# UniSeb8266.net
KiCad netlist of a schematic drawn in EAGLE
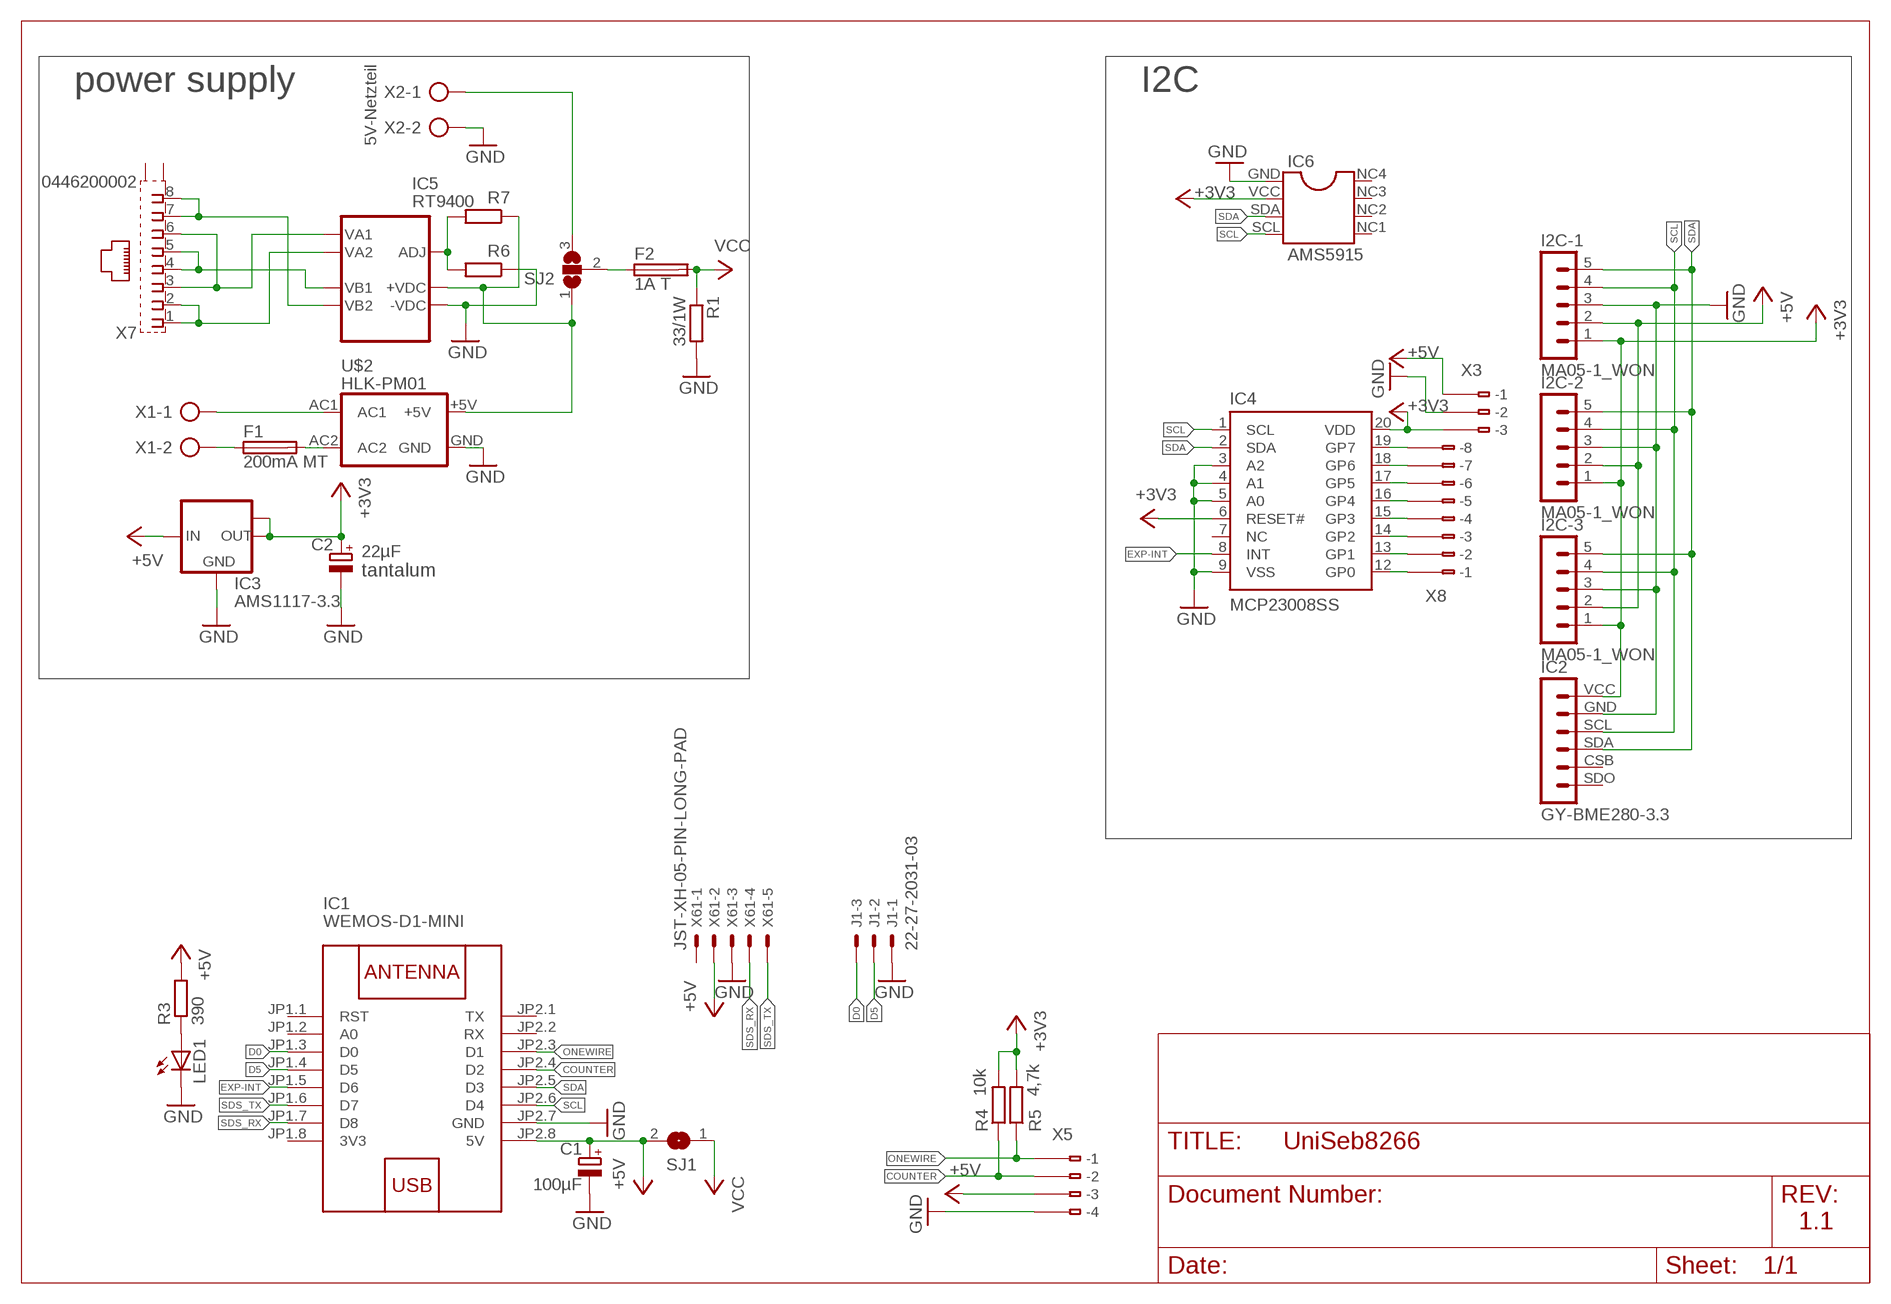
[diagram p0: schematic, sheet 1]

(export (version "E")
  (design (tool "Eeschema 10.0.6"))
  (components
    (comp (ref "C1")
      (value "100µF")
      (footprint "eagle-import:E2,5-6")
      (libsource (lib "eagle-import") (part "CPOL-EUE2.5-6"))
    )
    (comp (ref "C2")
      (value "22µF")
      (footprint "eagle-import:E2,5-6")
      (libsource (lib "eagle-import") (part "CPOL-EUE2.5-6"))
    )
    (comp (ref "F1")
      (value "200mA MT")
      (footprint "eagle-import:TR5")
      (libsource (lib "eagle-import") (part "TR5"))
    )
    (comp (ref "F2")
      (value "1A T")
      (footprint "eagle-import:TR5")
      (libsource (lib "eagle-import") (part "TR5"))
    )
    (comp (ref "I2C-1")
      (value "MA05-1_WON")
      (footprint "eagle-import:MA05-1_WON")
      (libsource (lib "eagle-import") (part "MA05-1_WON"))
    )
    (comp (ref "I2C-2")
      (value "MA05-1_WON")
      (footprint "eagle-import:MA05-1_WON")
      (libsource (lib "eagle-import") (part "MA05-1_WON"))
    )
    (comp (ref "I2C-3")
      (value "MA05-1_WON")
      (footprint "eagle-import:MA05-1_WON")
      (libsource (lib "eagle-import") (part "MA05-1_WON"))
    )
    (comp (ref "IC1")
      (value "WEMOS-D1-MINI")
      (footprint "eagle-import:WEMOS-D1-MINI")
      (libsource (lib "eagle-import") (part "WEMOS-D1-MINI"))
    )
    (comp (ref "IC2")
      (value "GY-BME280-3.3")
      (footprint "eagle-import:GY-BME280-3.3")
      (libsource (lib "eagle-import") (part "GY-BME280-3.3"))
    )
    (comp (ref "IC3")
      (value "AMS1117-3.3")
      (footprint "eagle-import:SOT223")
      (libsource (lib "eagle-import") (part "LM1117IMPX-3.3"))
    )
    (comp (ref "IC4")
      (value "MCP23008SS")
      (footprint "eagle-import:SSOP20")
      (libsource (lib "eagle-import") (part "MCP23008SS"))
    )
    (comp (ref "IC5")
      (value "RT9400")
      (footprint "eagle-import:RT9400")
      (libsource (lib "eagle-import") (part "RT9400"))
    )
    (comp (ref "IC6")
      (value "AMS5915")
      (footprint "eagle-import:AMS5915")
      (libsource (lib "eagle-import") (part "AMS5915"))
    )
    (comp (ref "J1")
      (value "22-27-2031-03")
      (footprint "eagle-import:6410-03")
      (libsource (lib "eagle-import") (part "22-?-0327-2031"))
    )
    (comp (ref "LED1")
      (value "LED3MM")
      (footprint "eagle-import:LED3MM")
      (libsource (lib "eagle-import") (part "LED3MM"))
    )
    (comp (ref "R1")
      (value "33/1W")
      (footprint "eagle-import:P0613V")
      (libsource (lib "eagle-import") (part "resistor_R-EU_0613/5V"))
    )
    (comp (ref "R3")
      (value "390")
      (footprint "eagle-import:R1206")
      (libsource (lib "eagle-import") (part "R-EU_R1206"))
    )
    (comp (ref "R4")
      (value "10k")
      (footprint "eagle-import:R1206")
      (libsource (lib "eagle-import") (part "R-EU_R1206"))
    )
    (comp (ref "R5")
      (value "4,7k")
      (footprint "eagle-import:R1206")
      (libsource (lib "eagle-import") (part "R-EU_R1206"))
    )
    (comp (ref "R6")
      (value "R-EU_R1206")
      (footprint "eagle-import:R1206")
      (libsource (lib "eagle-import") (part "R-EU_R1206"))
    )
    (comp (ref "R7")
      (value "R-EU_R1206")
      (footprint "eagle-import:R1206")
      (libsource (lib "eagle-import") (part "R-EU_R1206"))
    )
    (comp (ref "SJ1") (value "SJ") (footprint "eagle-import:SJ") (libsource (lib "eagle-import") (part "SJ")))
    (comp (ref "SJ2")
      (value "SJ2W")
      (footprint "eagle-import:SJ_2")
      (libsource (lib "eagle-import") (part "SJ2W"))
    )
    (comp (ref "U$2")
      (value "HLK-PM01")
      (footprint "eagle-import:HLK-PM01")
      (libsource (lib "eagle-import") (part "HLK-PM01"))
    )
    (comp (ref "X1")
      (value "AK500/2")
      (footprint "eagle-import:AK500_2")
      (libsource (lib "eagle-import") (part "AK500/2"))
    )
    (comp (ref "X2")
      (value "AK500/2")
      (footprint "eagle-import:AK500_2")
      (libsource (lib "eagle-import") (part "AK500/2"))
    )
    (comp (ref "X3")
      (value "233-503")
      (footprint "eagle-import:233-503")
      (fields (field (name "MF") "Wago Corporation") (field (name "MPN") "0233-0503"))
      (libsource (lib "eagle-import") (part "233-503"))
    )
    (comp (ref "X5")
      (value "233-504")
      (footprint "eagle-import:233-504")
      (fields (field (name "MF") "Wago Corporation") (field (name "MPN") "0233-0504"))
      (libsource (lib "eagle-import") (part "233-504"))
    )
    (comp (ref "X7")
      (value "0446200002")
      (footprint "eagle-import:0446200002")
      (fields (field (name "MF") "MOLEX"))
      (libsource (lib "eagle-import") (part "0446200002"))
    )
    (comp (ref "X8")
      (value "233-508")
      (footprint "eagle-import:233-508")
      (fields (field (name "MF") "Wago Corporation") (field (name "MPN") "0233-0508"))
      (libsource (lib "eagle-import") (part "233-508"))
    )
    (comp (ref "X61")
      (value "JST-XH-05-PIN-LONG-PAD")
      (footprint "eagle-import:JST-XH-05-PACKAGE-LONG-PAD")
      (libsource (lib "eagle-import") (part "JST-XH-05-PIN-LONG-PAD"))
    )
  )
  (nets
    (net (code "1") (name "+3V3") (class "Default")
      (node (ref "C2") (pin "+") (pinfunction "+_+") (pintype "passive"))
      (node (ref "I2C-1") (pin "1") (pinfunction "1_1") (pintype "passive"))
      (node (ref "I2C-2") (pin "1") (pinfunction "1_1") (pintype "passive"))
      (node (ref "I2C-3") (pin "1") (pinfunction "1_1") (pintype "passive"))
      (node (ref "IC2") (pin "VCC") (pinfunction "VCC_VCC") (pintype "passive"))
      (node (ref "IC3") (pin "2") (pinfunction "OUT_2") (pintype "passive"))
      (node (ref "IC3") (pin "TAB") (pinfunction "OUT1_TAB") (pintype "passive"))
      (node (ref "IC4") (pin "20") (pinfunction "VDD_20") (pintype "power_in"))
      (node (ref "IC4") (pin "6") (pinfunction "RESET#_6") (pintype "input"))
      (node (ref "IC6") (pin "VCC") (pinfunction "2_VCC") (pintype "passive"))
      (node (ref "R4") (pin "2") (pinfunction "2_2") (pintype "passive"))
      (node (ref "R5") (pin "2") (pinfunction "2_2") (pintype "passive"))
      (node (ref "X3") (pin "B3") (pinfunction "B-3_B3") (pintype "passive"))
    )
    (net (code "2") (name "+5V") (class "Default")
      (node (ref "C1") (pin "+") (pinfunction "+_+") (pintype "passive"))
      (node (ref "I2C-1") (pin "2") (pinfunction "2_2") (pintype "passive"))
      (node (ref "I2C-2") (pin "2") (pinfunction "2_2") (pintype "passive"))
      (node (ref "I2C-3") (pin "2") (pinfunction "2_2") (pintype "passive"))
      (node (ref "IC1") (pin "JP2.8") (pinfunction "5V_JP2.8") (pintype "power_in"))
      (node (ref "IC3") (pin "3") (pinfunction "IN_3") (pintype "input"))
      (node (ref "R3") (pin "2") (pinfunction "2_2") (pintype "passive"))
      (node (ref "SJ1") (pin "2") (pinfunction "2_2") (pintype "passive"))
      (node (ref "X3") (pin "B1") (pinfunction "B-1_B1") (pintype "passive"))
      (node (ref "X5") (pin "B3") (pinfunction "B-3_B3") (pintype "passive"))
      (node (ref "X61") (pin "2") (pinfunction "S_2") (pintype "passive"))
    )
    (net (code "3") (name "/3V3") (class "Default")
      (node (ref "IC1") (pin "JP1.8") (pinfunction "3V3_JP1.8") (pintype "power_in"))
    )
    (net (code "4") (name "COUNTER") (class "Default")
      (node (ref "IC1") (pin "JP2.4") (pinfunction "D2_JP2.4") (pintype "bidirectional"))
      (node (ref "R4") (pin "1") (pinfunction "1_1") (pintype "passive"))
      (node (ref "X5") (pin "B2") (pinfunction "B-2_B2") (pintype "passive"))
    )
    (net (code "5") (name "D0") (class "Default")
      (node (ref "IC1") (pin "JP1.3") (pinfunction "D0_JP1.3") (pintype "bidirectional"))
      (node (ref "J1") (pin "3") (pinfunction "S_3") (pintype "passive"))
    )
    (net (code "6") (name "D5") (class "Default")
      (node (ref "IC1") (pin "JP1.4") (pinfunction "D5_JP1.4") (pintype "bidirectional"))
      (node (ref "J1") (pin "2") (pinfunction "S_2") (pintype "passive"))
    )
    (net (code "7") (name "EXP-INT") (class "Default")
      (node (ref "IC1") (pin "JP1.5") (pinfunction "D6_JP1.5") (pintype "bidirectional"))
      (node (ref "IC4") (pin "8") (pinfunction "INT_8") (pintype "output"))
    )
    (net (code "8") (name "GND") (class "Default")
      (node (ref "C1") (pin "-") (pinfunction "-_-") (pintype "passive"))
      (node (ref "C2") (pin "-") (pinfunction "-_-") (pintype "passive"))
      (node (ref "I2C-1") (pin "3") (pinfunction "3_3") (pintype "passive"))
      (node (ref "I2C-2") (pin "3") (pinfunction "3_3") (pintype "passive"))
      (node (ref "I2C-3") (pin "3") (pinfunction "3_3") (pintype "passive"))
      (node (ref "IC1") (pin "JP2.7") (pinfunction "GND_JP2.7") (pintype "power_in"))
      (node (ref "IC2") (pin "GND") (pinfunction "GND_GND") (pintype "passive"))
      (node (ref "IC3") (pin "1") (pinfunction "GND_1") (pintype "input"))
      (node (ref "IC4") (pin "3") (pinfunction "A2_3") (pintype "input"))
      (node (ref "IC4") (pin "4") (pinfunction "A1_4") (pintype "input"))
      (node (ref "IC4") (pin "5") (pinfunction "A0_5") (pintype "input"))
      (node (ref "IC4") (pin "9") (pinfunction "VSS_9") (pintype "power_in"))
      (node (ref "IC5") (pin "P$5") (pinfunction "-VDC_P$5") (pintype "output"))
      (node (ref "IC6") (pin "GND") (pinfunction "1_GND") (pintype "passive"))
      (node (ref "J1") (pin "1") (pinfunction "S_1") (pintype "passive"))
      (node (ref "LED1") (pin "K") (pinfunction "C_K") (pintype "passive"))
      (node (ref "R1") (pin "2") (pinfunction "2_2") (pintype "passive"))
      (node (ref "R6") (pin "1") (pinfunction "1_1") (pintype "passive"))
      (node (ref "U$2") (pin "GND") (pinfunction "GND_GND") (pintype "passive"))
      (node (ref "X2") (pin "2") (pinfunction "KL_2") (pintype "passive"))
      (node (ref "X3") (pin "B2") (pinfunction "B-2_B2") (pintype "passive"))
      (node (ref "X5") (pin "B4") (pinfunction "B-4_B4") (pintype "passive"))
      (node (ref "X61") (pin "3") (pinfunction "S_3") (pintype "passive"))
    )
    (net (code "9") (name "Net-(F1-Pad2)") (class "Default")
      (node (ref "F1") (pin "2") (pinfunction "2_2") (pintype "passive"))
      (node (ref "U$2") (pin "AC2") (pinfunction "AC2_AC2") (pintype "input"))
    )
    (net (code "10") (name "Net-(F2-Pad1)") (class "Default")
      (node (ref "F2") (pin "1") (pinfunction "1_1") (pintype "passive"))
      (node (ref "SJ2") (pin "2") (pinfunction "2_2") (pintype "passive"))
    )
    (net (code "11") (name "Net-(IC4-GP0)") (class "Default")
      (node (ref "IC4") (pin "12") (pinfunction "GP0_12") (pintype "bidirectional"))
      (node (ref "X8") (pin "B1") (pinfunction "B-1_B1") (pintype "passive"))
    )
    (net (code "12") (name "Net-(IC4-GP1)") (class "Default")
      (node (ref "IC4") (pin "13") (pinfunction "GP1_13") (pintype "bidirectional"))
      (node (ref "X8") (pin "B2") (pinfunction "B-2_B2") (pintype "passive"))
    )
    (net (code "13") (name "Net-(IC4-GP2)") (class "Default")
      (node (ref "IC4") (pin "14") (pinfunction "GP2_14") (pintype "bidirectional"))
      (node (ref "X8") (pin "B3") (pinfunction "B-3_B3") (pintype "passive"))
    )
    (net (code "14") (name "Net-(IC4-GP3)") (class "Default")
      (node (ref "IC4") (pin "15") (pinfunction "GP3_15") (pintype "bidirectional"))
      (node (ref "X8") (pin "B4") (pinfunction "B-4_B4") (pintype "passive"))
    )
    (net (code "15") (name "Net-(IC4-GP4)") (class "Default")
      (node (ref "IC4") (pin "16") (pinfunction "GP4_16") (pintype "bidirectional"))
      (node (ref "X8") (pin "B5") (pinfunction "B-5_B5") (pintype "passive"))
    )
    (net (code "16") (name "Net-(IC4-GP5)") (class "Default")
      (node (ref "IC4") (pin "17") (pinfunction "GP5_17") (pintype "bidirectional"))
      (node (ref "X8") (pin "B6") (pinfunction "B-6_B6") (pintype "passive"))
    )
    (net (code "17") (name "Net-(IC4-GP6)") (class "Default")
      (node (ref "IC4") (pin "18") (pinfunction "GP6_18") (pintype "bidirectional"))
      (node (ref "X8") (pin "B7") (pinfunction "B-7_B7") (pintype "passive"))
    )
    (net (code "18") (name "Net-(IC4-GP7)") (class "Default")
      (node (ref "IC4") (pin "19") (pinfunction "GP7_19") (pintype "bidirectional"))
      (node (ref "X8") (pin "B8") (pinfunction "B-8_B8") (pintype "passive"))
    )
    (net (code "19") (name "Net-(IC5-+VDC)") (class "Default")
      (node (ref "IC5") (pin "P$6") (pinfunction "+VDC_P$6") (pintype "output"))
      (node (ref "R7") (pin "1") (pinfunction "1_1") (pintype "passive"))
      (node (ref "SJ2") (pin "1") (pinfunction "1_1") (pintype "passive"))
      (node (ref "U$2") (pin "+5V") (pinfunction "+5V_+5V") (pintype "passive"))
    )
    (net (code "20") (name "Net-(IC5-ADJ)") (class "Default")
      (node (ref "IC5") (pin "P$7") (pinfunction "ADJ_P$7") (pintype "output"))
      (node (ref "R6") (pin "2") (pinfunction "2_2") (pintype "passive"))
      (node (ref "R7") (pin "2") (pinfunction "2_2") (pintype "passive"))
    )
    (net (code "21") (name "Net-(IC5-VA1)") (class "Default")
      (node (ref "IC5") (pin "P$1") (pinfunction "VA1_P$1") (pintype "input"))
      (node (ref "X7") (pin "3") (pinfunction "3_3") (pintype "passive"))
      (node (ref "X7") (pin "6") (pinfunction "6_6") (pintype "passive"))
    )
    (net (code "22") (name "Net-(IC5-VA2)") (class "Default")
      (node (ref "IC5") (pin "P$2") (pinfunction "VA2_P$2") (pintype "input"))
      (node (ref "X7") (pin "1") (pinfunction "1_1") (pintype "passive"))
      (node (ref "X7") (pin "2") (pinfunction "2_2") (pintype "passive"))
    )
    (net (code "23") (name "Net-(IC5-VB1)") (class "Default")
      (node (ref "IC5") (pin "P$3") (pinfunction "VB1_P$3") (pintype "input"))
      (node (ref "X7") (pin "4") (pinfunction "4_4") (pintype "passive"))
      (node (ref "X7") (pin "5") (pinfunction "5_5") (pintype "passive"))
    )
    (net (code "24") (name "Net-(IC5-VB2)") (class "Default")
      (node (ref "IC5") (pin "P$4") (pinfunction "VB2_P$4") (pintype "input"))
      (node (ref "X7") (pin "7") (pinfunction "7_7") (pintype "passive"))
      (node (ref "X7") (pin "8") (pinfunction "8_8") (pintype "passive"))
    )
    (net (code "25") (name "Net-(LED1-PadA)") (class "Default")
      (node (ref "LED1") (pin "A") (pinfunction "A_A") (pintype "passive"))
      (node (ref "R3") (pin "1") (pinfunction "1_1") (pintype "passive"))
    )
    (net (code "26") (name "Net-(X1A-KL)") (class "Default")
      (node (ref "U$2") (pin "AC1") (pinfunction "AC1_AC1") (pintype "input"))
      (node (ref "X1") (pin "1") (pinfunction "KL_1") (pintype "passive"))
    )
    (net (code "27") (name "Net-(X1B-KL)") (class "Default")
      (node (ref "F1") (pin "1") (pinfunction "1_1") (pintype "passive"))
      (node (ref "X1") (pin "2") (pinfunction "KL_2") (pintype "passive"))
    )
    (net (code "28") (name "Net-(X2A-KL)") (class "Default")
      (node (ref "SJ2") (pin "3") (pinfunction "3_3") (pintype "passive"))
      (node (ref "X2") (pin "1") (pinfunction "KL_1") (pintype "passive"))
    )
    (net (code "29") (name "ONEWIRE") (class "Default")
      (node (ref "IC1") (pin "JP2.3") (pinfunction "D1_JP2.3") (pintype "bidirectional"))
      (node (ref "R5") (pin "1") (pinfunction "1_1") (pintype "passive"))
      (node (ref "X5") (pin "B1") (pinfunction "B-1_B1") (pintype "passive"))
    )
    (net (code "30") (name "SCL") (class "Default")
      (node (ref "I2C-1") (pin "4") (pinfunction "4_4") (pintype "passive"))
      (node (ref "I2C-2") (pin "4") (pinfunction "4_4") (pintype "passive"))
      (node (ref "I2C-3") (pin "4") (pinfunction "4_4") (pintype "passive"))
      (node (ref "IC1") (pin "JP2.6") (pinfunction "D4_JP2.6") (pintype "bidirectional"))
      (node (ref "IC2") (pin "SCL") (pinfunction "SCL_SCL") (pintype "passive"))
      (node (ref "IC4") (pin "1") (pinfunction "SCL_1") (pintype "input"))
      (node (ref "IC6") (pin "SCL") (pinfunction "4_SCL") (pintype "passive"))
    )
    (net (code "31") (name "SDA") (class "Default")
      (node (ref "I2C-1") (pin "5") (pinfunction "5_5") (pintype "passive"))
      (node (ref "I2C-2") (pin "5") (pinfunction "5_5") (pintype "passive"))
      (node (ref "I2C-3") (pin "5") (pinfunction "5_5") (pintype "passive"))
      (node (ref "IC1") (pin "JP2.5") (pinfunction "D3_JP2.5") (pintype "bidirectional"))
      (node (ref "IC2") (pin "SDA") (pinfunction "SDA_SDA") (pintype "passive"))
      (node (ref "IC4") (pin "2") (pinfunction "SDA_2") (pintype "bidirectional"))
      (node (ref "IC6") (pin "SDA") (pinfunction "3_SDA") (pintype "passive"))
    )
    (net (code "32") (name "SDS_RX") (class "Default")
      (node (ref "IC1") (pin "JP1.7") (pinfunction "D8_JP1.7") (pintype "bidirectional"))
      (node (ref "X61") (pin "4") (pinfunction "S_4") (pintype "passive"))
    )
    (net (code "33") (name "SDS_TX") (class "Default")
      (node (ref "IC1") (pin "JP1.6") (pinfunction "D7_JP1.6") (pintype "bidirectional"))
      (node (ref "X61") (pin "5") (pinfunction "S_5") (pintype "passive"))
    )
    (net (code "34") (name "VCC") (class "Default")
      (node (ref "F2") (pin "2") (pinfunction "2_2") (pintype "passive"))
      (node (ref "R1") (pin "1") (pinfunction "1_1") (pintype "passive"))
      (node (ref "SJ1") (pin "1") (pinfunction "1_1") (pintype "passive"))
    )
    (net (code "35") (name "unconnected-(IC1-A0-PadJP1.2)") (class "Default")
      (node (ref "IC1") (pin "JP1.2") (pinfunction "A0_JP1.2") (pintype "bidirectional"))
    )
    (net (code "36") (name "unconnected-(IC1-RST-PadJP1.1)") (class "Default")
      (node (ref "IC1") (pin "JP1.1") (pinfunction "RST_JP1.1") (pintype "bidirectional"))
    )
    (net (code "37") (name "unconnected-(IC1-RX-PadJP2.2)") (class "Default")
      (node (ref "IC1") (pin "JP2.2") (pinfunction "RX_JP2.2") (pintype "bidirectional"))
    )
    (net (code "38") (name "unconnected-(IC1-TX-PadJP2.1)") (class "Default")
      (node (ref "IC1") (pin "JP2.1") (pinfunction "TX_JP2.1") (pintype "bidirectional"))
    )
    (net (code "39") (name "unconnected-(IC2-PadCSB)") (class "Default")
      (node (ref "IC2") (pin "CSB") (pinfunction "CSB_CSB") (pintype "passive"))
    )
    (net (code "40") (name "unconnected-(IC2-PadSDO)") (class "Default")
      (node (ref "IC2") (pin "SDO") (pinfunction "SDO_SDO") (pintype "passive"))
    )
    (net (code "41") (name "unconnected-(IC4-NC-Pad7)") (class "Default")
      (node (ref "IC4") (pin "7") (pinfunction "NC_7") (pintype "no_connect"))
    )
    (net (code "42") (name "unconnected-(IC6-5-PadNC1)") (class "Default")
      (node (ref "IC6") (pin "NC1") (pinfunction "5_NC1") (pintype "passive"))
    )
    (net (code "43") (name "unconnected-(IC6-6-PadNC2)") (class "Default")
      (node (ref "IC6") (pin "NC2") (pinfunction "6_NC2") (pintype "passive"))
    )
    (net (code "44") (name "unconnected-(IC6-7-PadNC3)") (class "Default")
      (node (ref "IC6") (pin "NC3") (pinfunction "7_NC3") (pintype "passive"))
    )
    (net (code "45") (name "unconnected-(IC6-8-PadNC4)") (class "Default")
      (node (ref "IC6") (pin "NC4") (pinfunction "8_NC4") (pintype "passive"))
    )
    (net (code "46") (name "unconnected-(X3--1-PadA1)") (class "Default")
      (node (ref "X3") (pin "A1") (pinfunction "-1_A1") (pintype "passive"))
    )
    (net (code "47") (name "unconnected-(X3--2-PadA2)") (class "Default")
      (node (ref "X3") (pin "A2") (pinfunction "-2_A2") (pintype "passive"))
    )
    (net (code "48") (name "unconnected-(X3--3-PadA3)") (class "Default")
      (node (ref "X3") (pin "A3") (pinfunction "-3_A3") (pintype "passive"))
    )
    (net (code "49") (name "unconnected-(X5--1-PadA1)") (class "Default")
      (node (ref "X5") (pin "A1") (pinfunction "-1_A1") (pintype "passive"))
    )
    (net (code "50") (name "unconnected-(X5--2-PadA2)") (class "Default")
      (node (ref "X5") (pin "A2") (pinfunction "-2_A2") (pintype "passive"))
    )
    (net (code "51") (name "unconnected-(X5--3-PadA3)") (class "Default")
      (node (ref "X5") (pin "A3") (pinfunction "-3_A3") (pintype "passive"))
    )
    (net (code "52") (name "unconnected-(X5--4-PadA4)") (class "Default")
      (node (ref "X5") (pin "A4") (pinfunction "-4_A4") (pintype "passive"))
    )
    (net (code "53") (name "unconnected-(X7-S1-PadS@1)") (class "Default")
      (node (ref "X7") (pin "S@1") (pinfunction "S1_S@1") (pintype "passive"))
    )
    (net (code "54") (name "unconnected-(X7-S2-PadS@2)") (class "Default")
      (node (ref "X7") (pin "S@2") (pinfunction "S2_S@2") (pintype "passive"))
    )
    (net (code "55") (name "unconnected-(X8--1-PadA1)") (class "Default")
      (node (ref "X8") (pin "A1") (pinfunction "-1_A1") (pintype "passive"))
    )
    (net (code "56") (name "unconnected-(X8--2-PadA2)") (class "Default")
      (node (ref "X8") (pin "A2") (pinfunction "-2_A2") (pintype "passive"))
    )
    (net (code "57") (name "unconnected-(X8--3-PadA3)") (class "Default")
      (node (ref "X8") (pin "A3") (pinfunction "-3_A3") (pintype "passive"))
    )
    (net (code "58") (name "unconnected-(X8--4-PadA4)") (class "Default")
      (node (ref "X8") (pin "A4") (pinfunction "-4_A4") (pintype "passive"))
    )
    (net (code "59") (name "unconnected-(X8--5-PadA5)") (class "Default")
      (node (ref "X8") (pin "A5") (pinfunction "-5_A5") (pintype "passive"))
    )
    (net (code "60") (name "unconnected-(X8--6-PadA6)") (class "Default")
      (node (ref "X8") (pin "A6") (pinfunction "-6_A6") (pintype "passive"))
    )
    (net (code "61") (name "unconnected-(X8--7-PadA7)") (class "Default")
      (node (ref "X8") (pin "A7") (pinfunction "-7_A7") (pintype "passive"))
    )
    (net (code "62") (name "unconnected-(X8--8-PadA8)") (class "Default")
      (node (ref "X8") (pin "A8") (pinfunction "-8_A8") (pintype "passive"))
    )
    (net (code "63") (name "unconnected-(X61A-S-Pad1)") (class "Default")
      (node (ref "X61") (pin "1") (pinfunction "S_1") (pintype "passive"))
    )
  )
)
